# P_07__CPU_PHY.net
KiCad netlist of a schematic drawn in Altium Designer
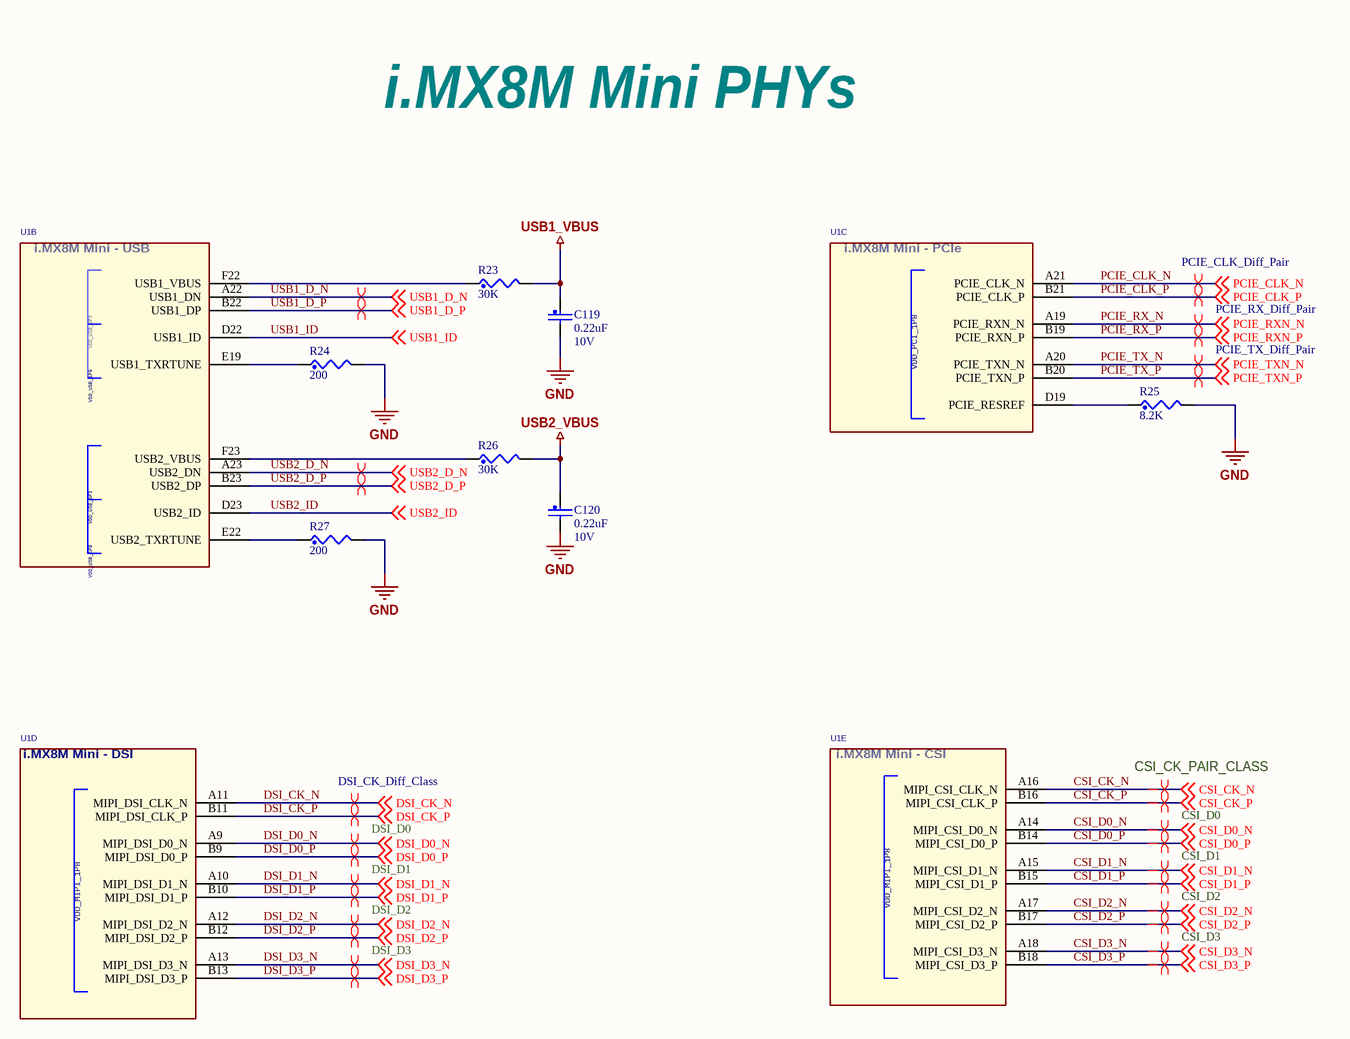
[diagram p0: P[07]_CPU_PHY.SchDoc]

(export (version "E")
  (design (tool "Eeschema 10.0.6"))
  (components
    (comp (ref "C119")
      (value "0.22uF")
      (footprint "0201_CC - C")
      (fields (field (name "VOLTAGE") "10V"))
      (libsource (lib "AA_iMX8_M_") (part "CAP_NP"))
    )
    (comp (ref "C120")
      (value "0.22uF")
      (footprint "0201_CC - C")
      (fields (field (name "VOLTAGE") "10V"))
      (libsource (lib "AA_iMX8_M_") (part "CAP_NP"))
    )
    (comp (ref "R23") (value "30K") (footprint "0201_CC") (libsource (lib "AA_iMX8_M_") (part "RES")))
    (comp (ref "R24") (value "200") (footprint "0201_CC") (libsource (lib "AA_iMX8_M_") (part "RES")))
    (comp (ref "R25") (value "8.2K") (footprint "0402_CC") (libsource (lib "AA_iMX8_M_") (part "RES")))
    (comp (ref "R26") (value "30K") (footprint "0201_CC") (libsource (lib "AA_iMX8_M_") (part "RES")))
    (comp (ref "R27") (value "200") (footprint "0201_CC") (libsource (lib "AA_iMX8_M_") (part "RES")))
    (comp (ref "U1")
      (value "~")
      (footprint "BGA486_0P5_14X14")
      (description "IC CPU QUAD CORTEX A53+M4 1.8GHZ BGA486 / By Arman Arvand")
      (libsource (lib "AA_iMX8_M_") (part "MIMX8MM_BGA486P"))
    )
  )
  (nets
    (net (code "1") (name "CSI_CK_N") (class "Default")
      (node (ref "U1") (pin "A16") (pinfunction "MIPI_CSI_CLK_N_A16") (pintype "passive"))
    )
    (net (code "2") (name "CSI_CK_P") (class "Default")
      (node (ref "U1") (pin "B16") (pinfunction "MIPI_CSI_CLK_P_B16") (pintype "passive"))
    )
    (net (code "3") (name "CSI_D0_N") (class "Default")
      (node (ref "U1") (pin "A14") (pinfunction "MIPI_CSI_D0_N_A14") (pintype "passive"))
    )
    (net (code "4") (name "CSI_D0_P") (class "Default")
      (node (ref "U1") (pin "B14") (pinfunction "MIPI_CSI_D0_P_B14") (pintype "passive"))
    )
    (net (code "5") (name "CSI_D1_N") (class "Default")
      (node (ref "U1") (pin "A15") (pinfunction "MIPI_CSI_D1_N_A15") (pintype "passive"))
    )
    (net (code "6") (name "CSI_D1_P") (class "Default")
      (node (ref "U1") (pin "B15") (pinfunction "MIPI_CSI_D1_P_B15") (pintype "passive"))
    )
    (net (code "7") (name "CSI_D2_N") (class "Default")
      (node (ref "U1") (pin "A17") (pinfunction "MIPI_CSI_D2_N_A17") (pintype "passive"))
    )
    (net (code "8") (name "CSI_D2_P") (class "Default")
      (node (ref "U1") (pin "B17") (pinfunction "MIPI_CSI_D2_P_B17") (pintype "passive"))
    )
    (net (code "9") (name "CSI_D3_N") (class "Default")
      (node (ref "U1") (pin "A18") (pinfunction "MIPI_CSI_D3_N_A18") (pintype "passive"))
    )
    (net (code "10") (name "CSI_D3_P") (class "Default")
      (node (ref "U1") (pin "B18") (pinfunction "MIPI_CSI_D3_P_B18") (pintype "passive"))
    )
    (net (code "11") (name "DSI_CK_N") (class "Default")
      (node (ref "U1") (pin "A11") (pinfunction "MIPI_DSI_CLK_N_A11") (pintype "passive"))
    )
    (net (code "12") (name "DSI_CK_P") (class "Default")
      (node (ref "U1") (pin "B11") (pinfunction "MIPI_DSI_CLK_P_B11") (pintype "passive"))
    )
    (net (code "13") (name "DSI_D0_N") (class "Default")
      (node (ref "U1") (pin "A9") (pinfunction "MIPI_DSI_D0_N_A9") (pintype "passive"))
    )
    (net (code "14") (name "DSI_D0_P") (class "Default")
      (node (ref "U1") (pin "B9") (pinfunction "MIPI_DSI_D0_P_B9") (pintype "passive"))
    )
    (net (code "15") (name "DSI_D1_N") (class "Default")
      (node (ref "U1") (pin "A10") (pinfunction "MIPI_DSI_D1_N_A10") (pintype "passive"))
    )
    (net (code "16") (name "DSI_D1_P") (class "Default")
      (node (ref "U1") (pin "B10") (pinfunction "MIPI_DSI_D1_P_B10") (pintype "passive"))
    )
    (net (code "17") (name "DSI_D2_N") (class "Default")
      (node (ref "U1") (pin "A12") (pinfunction "MIPI_DSI_D2_N_A12") (pintype "passive"))
    )
    (net (code "18") (name "DSI_D2_P") (class "Default")
      (node (ref "U1") (pin "B12") (pinfunction "MIPI_DSI_D2_P_B12") (pintype "passive"))
    )
    (net (code "19") (name "DSI_D3_N") (class "Default")
      (node (ref "U1") (pin "A13") (pinfunction "MIPI_DSI_D3_N_A13") (pintype "passive"))
    )
    (net (code "20") (name "DSI_D3_P") (class "Default")
      (node (ref "U1") (pin "B13") (pinfunction "MIPI_DSI_D3_P_B13") (pintype "passive"))
    )
    (net (code "21") (name "GND") (class "Default")
      (node (ref "C119") (pin "2") (pinfunction "2_2") (pintype "passive"))
      (node (ref "C120") (pin "2") (pinfunction "2_2") (pintype "passive"))
      (node (ref "R24") (pin "2") (pinfunction "2_2") (pintype "passive"))
      (node (ref "R25") (pin "2") (pinfunction "2_2") (pintype "passive"))
      (node (ref "R27") (pin "2") (pinfunction "2_2") (pintype "passive"))
    )
    (net (code "22") (name "Net-(U1B-USB1_TXRTUNE)") (class "Default")
      (node (ref "R24") (pin "1") (pinfunction "1_1") (pintype "passive"))
      (node (ref "U1") (pin "E19") (pinfunction "USB1_TXRTUNE_E19") (pintype "passive"))
    )
    (net (code "23") (name "Net-(U1B-USB1_VBUS)") (class "Default")
      (node (ref "R23") (pin "1") (pinfunction "1_1") (pintype "passive"))
      (node (ref "U1") (pin "F22") (pinfunction "USB1_VBUS_F22") (pintype "passive"))
    )
    (net (code "24") (name "Net-(U1B-USB2_TXRTUNE)") (class "Default")
      (node (ref "R27") (pin "1") (pinfunction "1_1") (pintype "passive"))
      (node (ref "U1") (pin "E22") (pinfunction "USB2_TXRTUNE_E22") (pintype "passive"))
    )
    (net (code "25") (name "Net-(U1B-USB2_VBUS)") (class "Default")
      (node (ref "R26") (pin "1") (pinfunction "1_1") (pintype "passive"))
      (node (ref "U1") (pin "F23") (pinfunction "USB2_VBUS_F23") (pintype "power_in"))
    )
    (net (code "26") (name "Net-(U1C-PCIE_RESREF)") (class "Default")
      (node (ref "R25") (pin "1") (pinfunction "1_1") (pintype "passive"))
      (node (ref "U1") (pin "D19") (pinfunction "PCIE_RESREF_D19") (pintype "passive"))
    )
    (net (code "27") (name "PCIE_CLK_N") (class "Default")
      (node (ref "U1") (pin "A21") (pinfunction "PCIE_CLK_N_A21") (pintype "passive"))
    )
    (net (code "28") (name "PCIE_CLK_P") (class "Default")
      (node (ref "U1") (pin "B21") (pinfunction "PCIE_CLK_P_B21") (pintype "passive"))
    )
    (net (code "29") (name "PCIE_RXN_N") (class "Default")
      (node (ref "U1") (pin "A19") (pinfunction "PCIE_RXN_N_A19") (pintype "passive"))
    )
    (net (code "30") (name "PCIE_RXN_P") (class "Default")
      (node (ref "U1") (pin "B19") (pinfunction "PCIE_RXN_P_B19") (pintype "passive"))
    )
    (net (code "31") (name "PCIE_TXN_N") (class "Default")
      (node (ref "U1") (pin "A20") (pinfunction "PCIE_TXN_N_A20") (pintype "passive"))
    )
    (net (code "32") (name "PCIE_TXN_P") (class "Default")
      (node (ref "U1") (pin "B20") (pinfunction "PCIE_TXN_P_B20") (pintype "passive"))
    )
    (net (code "33") (name "USB1_D_N") (class "Default")
      (node (ref "U1") (pin "A22") (pinfunction "USB1_DN_A22") (pintype "passive"))
    )
    (net (code "34") (name "USB1_D_P") (class "Default")
      (node (ref "U1") (pin "B22") (pinfunction "USB1_DP_B22") (pintype "passive"))
    )
    (net (code "35") (name "USB1_ID") (class "Default")
      (node (ref "U1") (pin "D22") (pinfunction "USB1_ID_D22") (pintype "passive"))
    )
    (net (code "36") (name "USB1_VBUS") (class "Default")
      (node (ref "C119") (pin "1") (pinfunction "1_1") (pintype "passive"))
      (node (ref "R23") (pin "2") (pinfunction "2_2") (pintype "passive"))
    )
    (net (code "37") (name "USB2_D_N") (class "Default")
      (node (ref "U1") (pin "A23") (pinfunction "USB2_DN_A23") (pintype "passive"))
    )
    (net (code "38") (name "USB2_D_P") (class "Default")
      (node (ref "U1") (pin "B23") (pinfunction "USB2_DP_B23") (pintype "passive"))
    )
    (net (code "39") (name "USB2_ID") (class "Default")
      (node (ref "U1") (pin "D23") (pinfunction "USB2_ID_D23") (pintype "passive"))
    )
    (net (code "40") (name "USB2_VBUS") (class "Default")
      (node (ref "C120") (pin "1") (pinfunction "1_1") (pintype "passive"))
      (node (ref "R26") (pin "2") (pinfunction "2_2") (pintype "passive"))
    )
  )
)
